# LoRa-E5-Sensor.net
KiCad netlist of a schematic drawn in EAGLE
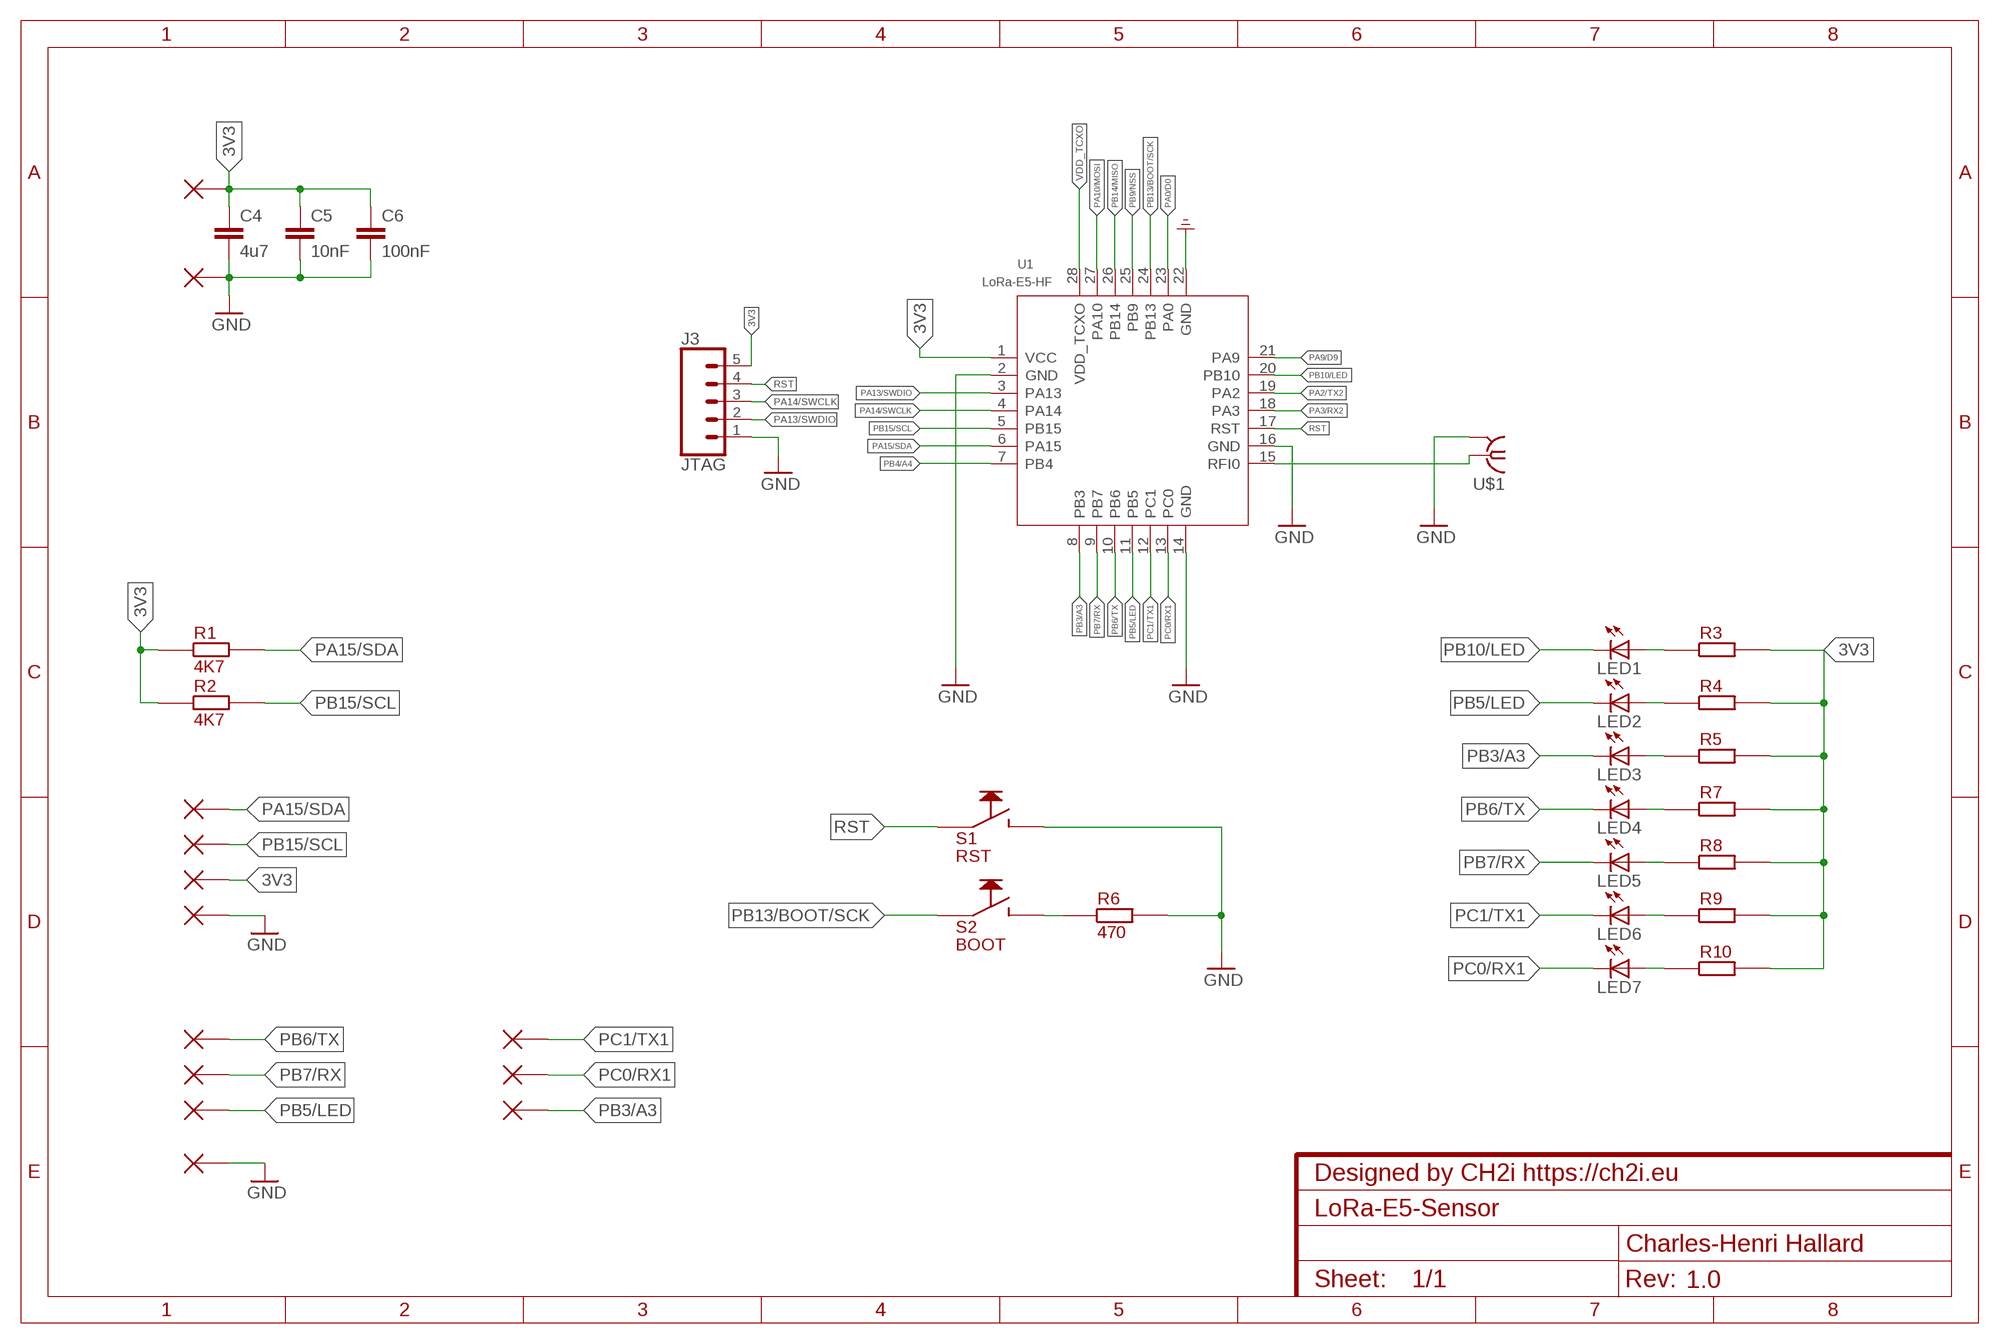
[diagram p0: schematic, sheet 1]

(export (version "E")
  (design (tool "Eeschema 10.0.6"))
  (components
    (comp (ref "C4")
      (value "4u7")
      (footprint "eagle-import:C1206")
      (libsource (lib "eagle-import") (part "SMD-C-1206"))
    )
    (comp (ref "C5")
      (value "10nF")
      (footprint "eagle-import:C1206")
      (libsource (lib "eagle-import") (part "SMD-C-1206"))
    )
    (comp (ref "C6")
      (value "100nF")
      (footprint "eagle-import:C1206")
      (libsource (lib "eagle-import") (part "SMD-C-1206"))
    )
    (comp (ref "J3")
      (value "JTAG")
      (footprint "eagle-import:1X05_LOCK")
      (libsource (lib "eagle-import") (part "CONN_05LOCK"))
    )
    (comp (ref "LED1")
      (value "SMD-LED-1206")
      (footprint "eagle-import:LED_1206")
      (libsource (lib "eagle-import") (part "SMD-LED-1206"))
    )
    (comp (ref "LED2")
      (value "SMD-LED-1206")
      (footprint "eagle-import:LED_1206")
      (libsource (lib "eagle-import") (part "SMD-LED-1206"))
    )
    (comp (ref "LED3")
      (value "SMD-LED-1206")
      (footprint "eagle-import:LED_1206")
      (libsource (lib "eagle-import") (part "SMD-LED-1206"))
    )
    (comp (ref "LED4")
      (value "SMD-LED-1206")
      (footprint "eagle-import:LED_1206")
      (libsource (lib "eagle-import") (part "SMD-LED-1206"))
    )
    (comp (ref "LED5")
      (value "SMD-LED-1206")
      (footprint "eagle-import:LED_1206")
      (libsource (lib "eagle-import") (part "SMD-LED-1206"))
    )
    (comp (ref "LED6")
      (value "SMD-LED-1206")
      (footprint "eagle-import:LED_1206")
      (libsource (lib "eagle-import") (part "SMD-LED-1206"))
    )
    (comp (ref "LED7")
      (value "SMD-LED-1206")
      (footprint "eagle-import:LED_1206")
      (libsource (lib "eagle-import") (part "SMD-LED-1206"))
    )
    (comp (ref "P1")
      (value "PIN")
      (footprint "eagle-import:PIN")
      (libsource (lib "eagle-import") (part "PIN"))
    )
    (comp (ref "P2")
      (value "PIN")
      (footprint "eagle-import:PIN")
      (libsource (lib "eagle-import") (part "PIN"))
    )
    (comp (ref "P3")
      (value "PIN")
      (footprint "eagle-import:PIN")
      (libsource (lib "eagle-import") (part "PIN"))
    )
    (comp (ref "P4")
      (value "PIN")
      (footprint "eagle-import:PIN")
      (libsource (lib "eagle-import") (part "PIN"))
    )
    (comp (ref "P5")
      (value "PIN")
      (footprint "eagle-import:PIN")
      (libsource (lib "eagle-import") (part "PIN"))
    )
    (comp (ref "P6")
      (value "PIN")
      (footprint "eagle-import:PIN")
      (libsource (lib "eagle-import") (part "PIN"))
    )
    (comp (ref "P7")
      (value "PIN")
      (footprint "eagle-import:PIN")
      (libsource (lib "eagle-import") (part "PIN"))
    )
    (comp (ref "P8")
      (value "PIN")
      (footprint "eagle-import:PIN")
      (libsource (lib "eagle-import") (part "PIN"))
    )
    (comp (ref "P9")
      (value "PIN")
      (footprint "eagle-import:PIN")
      (libsource (lib "eagle-import") (part "PIN"))
    )
    (comp (ref "P10")
      (value "PIN")
      (footprint "eagle-import:PIN")
      (libsource (lib "eagle-import") (part "PIN"))
    )
    (comp (ref "P11")
      (value "PIN")
      (footprint "eagle-import:PIN")
      (libsource (lib "eagle-import") (part "PIN"))
    )
    (comp (ref "P12")
      (value "PIN")
      (footprint "eagle-import:PIN")
      (libsource (lib "eagle-import") (part "PIN"))
    )
    (comp (ref "P13")
      (value "PIN")
      (footprint "eagle-import:PIN")
      (libsource (lib "eagle-import") (part "PIN"))
    )
    (comp (ref "R1")
      (value "4K7")
      (footprint "eagle-import:R0603")
      (libsource (lib "eagle-import") (part "SMD-RR0603"))
    )
    (comp (ref "R2")
      (value "4K7")
      (footprint "eagle-import:R0603")
      (libsource (lib "eagle-import") (part "SMD-RR0603"))
    )
    (comp (ref "R3")
      (value "SMD-RR0603")
      (footprint "eagle-import:R0603")
      (libsource (lib "eagle-import") (part "SMD-RR0603"))
    )
    (comp (ref "R4")
      (value "SMD-RR0603")
      (footprint "eagle-import:R0603")
      (libsource (lib "eagle-import") (part "SMD-RR0603"))
    )
    (comp (ref "R5")
      (value "SMD-RR0603")
      (footprint "eagle-import:R0603")
      (libsource (lib "eagle-import") (part "SMD-RR0603"))
    )
    (comp (ref "R6")
      (value "470")
      (footprint "eagle-import:C1206")
      (libsource (lib "eagle-import") (part "SMD-RR1206"))
    )
    (comp (ref "R7")
      (value "SMD-RR0603")
      (footprint "eagle-import:R0603")
      (libsource (lib "eagle-import") (part "SMD-RR0603"))
    )
    (comp (ref "R8")
      (value "SMD-RR0603")
      (footprint "eagle-import:R0603")
      (libsource (lib "eagle-import") (part "SMD-RR0603"))
    )
    (comp (ref "R9")
      (value "SMD-RR0603")
      (footprint "eagle-import:R0603")
      (libsource (lib "eagle-import") (part "SMD-RR0603"))
    )
    (comp (ref "R10")
      (value "SMD-RR0603")
      (footprint "eagle-import:R0603")
      (libsource (lib "eagle-import") (part "SMD-RR0603"))
    )
    (comp (ref "S1")
      (value "RST")
      (footprint "eagle-import:SMD-PUSH-BUTTON-ILS-3X6X2,5")
      (libsource (lib "eagle-import") (part "SMD-PUSH-BUTTONILS-3X6X2,5"))
    )
    (comp (ref "S2")
      (value "BOOT")
      (footprint "eagle-import:SMD-PUSH-BUTTON-ILS-3X6X2,5")
      (libsource (lib "eagle-import") (part "SMD-PUSH-BUTTONILS-3X6X2,5"))
    )
    (comp (ref "U$1")
      (value "SMAU.FL")
      (footprint "eagle-import:U.FL_SMT")
      (libsource (lib "eagle-import") (part "SMAU.FL"))
    )
    (comp (ref "U1")
      (value "LoRa-E5-HF")
      (footprint "eagle-import:MOUDLE28P-1.25-12X12X2.5MM")
      (libsource (lib "eagle-import") (part "MOUDLE_LORA_E5"))
    )
  )
  (nets
    (net (code "1") (name "3V3") (class "Default")
      (node (ref "C4") (pin "1") (pinfunction "1_1") (pintype "passive"))
      (node (ref "C5") (pin "1") (pinfunction "1_1") (pintype "passive"))
      (node (ref "C6") (pin "1") (pinfunction "1_1") (pintype "passive"))
      (node (ref "J3") (pin "5") (pinfunction "5_5") (pintype "passive"))
      (node (ref "P4") (pin "P$1") (pinfunction "P$1_P$1") (pintype "bidirectional"))
      (node (ref "P5") (pin "P$1") (pinfunction "P$1_P$1") (pintype "bidirectional"))
      (node (ref "R1") (pin "1") (pinfunction "P$1_1") (pintype "passive"))
      (node (ref "R10") (pin "2") (pinfunction "P$3_2") (pintype "passive"))
      (node (ref "R2") (pin "1") (pinfunction "P$1_1") (pintype "passive"))
      (node (ref "R3") (pin "2") (pinfunction "P$3_2") (pintype "passive"))
      (node (ref "R4") (pin "2") (pinfunction "P$3_2") (pintype "passive"))
      (node (ref "R5") (pin "2") (pinfunction "P$3_2") (pintype "passive"))
      (node (ref "R7") (pin "2") (pinfunction "P$3_2") (pintype "passive"))
      (node (ref "R8") (pin "2") (pinfunction "P$3_2") (pintype "passive"))
      (node (ref "R9") (pin "2") (pinfunction "P$3_2") (pintype "passive"))
      (node (ref "U1") (pin "1") (pinfunction "VCC_1") (pintype "bidirectional"))
    )
    (net (code "2") (name "GND") (class "Default")
      (node (ref "C4") (pin "2") (pinfunction "2_2") (pintype "passive"))
      (node (ref "C5") (pin "2") (pinfunction "2_2") (pintype "passive"))
      (node (ref "C6") (pin "2") (pinfunction "2_2") (pintype "passive"))
      (node (ref "J3") (pin "1") (pinfunction "1_1") (pintype "passive"))
      (node (ref "P1") (pin "P$1") (pinfunction "P$1_P$1") (pintype "bidirectional"))
      (node (ref "P6") (pin "P$1") (pinfunction "P$1_P$1") (pintype "bidirectional"))
      (node (ref "P9") (pin "P$1") (pinfunction "P$1_P$1") (pintype "bidirectional"))
      (node (ref "R6") (pin "2") (pinfunction "P$3_2") (pintype "passive"))
      (node (ref "S1") (pin "P$2") (pinfunction "P$2_P$2") (pintype "bidirectional"))
      (node (ref "U$1") (pin "GND1") (pinfunction "SHIELD_GND1") (pintype "passive"))
      (node (ref "U$1") (pin "GND2") (pinfunction "SHIELD_GND2") (pintype "passive"))
      (node (ref "U1") (pin "14") (pinfunction "GND_14") (pintype "bidirectional"))
      (node (ref "U1") (pin "16") (pinfunction "GND_16") (pintype "bidirectional"))
      (node (ref "U1") (pin "2") (pinfunction "GND_2") (pintype "bidirectional"))
      (node (ref "U1") (pin "22") (pinfunction "GND_22") (pintype "bidirectional"))
    )
    (net (code "3") (name "Net-(R3-P$1)") (class "Default")
      (node (ref "LED1") (pin "A") (pinfunction "A_A") (pintype "passive"))
      (node (ref "R3") (pin "1") (pinfunction "P$1_1") (pintype "passive"))
    )
    (net (code "4") (name "Net-(R4-P$1)") (class "Default")
      (node (ref "LED2") (pin "A") (pinfunction "A_A") (pintype "passive"))
      (node (ref "R4") (pin "1") (pinfunction "P$1_1") (pintype "passive"))
    )
    (net (code "5") (name "Net-(R5-P$1)") (class "Default")
      (node (ref "LED3") (pin "A") (pinfunction "A_A") (pintype "passive"))
      (node (ref "R5") (pin "1") (pinfunction "P$1_1") (pintype "passive"))
    )
    (net (code "6") (name "Net-(R6-P$1)") (class "Default")
      (node (ref "R6") (pin "1") (pinfunction "P$1_1") (pintype "passive"))
      (node (ref "S2") (pin "P$2") (pinfunction "P$2_P$2") (pintype "bidirectional"))
    )
    (net (code "7") (name "Net-(R7-P$1)") (class "Default")
      (node (ref "LED4") (pin "A") (pinfunction "A_A") (pintype "passive"))
      (node (ref "R7") (pin "1") (pinfunction "P$1_1") (pintype "passive"))
    )
    (net (code "8") (name "Net-(R8-P$1)") (class "Default")
      (node (ref "LED5") (pin "A") (pinfunction "A_A") (pintype "passive"))
      (node (ref "R8") (pin "1") (pinfunction "P$1_1") (pintype "passive"))
    )
    (net (code "9") (name "Net-(R9-P$1)") (class "Default")
      (node (ref "LED6") (pin "A") (pinfunction "A_A") (pintype "passive"))
      (node (ref "R9") (pin "1") (pinfunction "P$1_1") (pintype "passive"))
    )
    (net (code "10") (name "Net-(R10-P$1)") (class "Default")
      (node (ref "LED7") (pin "A") (pinfunction "A_A") (pintype "passive"))
      (node (ref "R10") (pin "1") (pinfunction "P$1_1") (pintype "passive"))
    )
    (net (code "11") (name "Net-(U$1-ANT)") (class "Default")
      (node (ref "U$1") (pin "SIG") (pinfunction "ANT_SIG") (pintype "passive"))
      (node (ref "U1") (pin "15") (pinfunction "RFI0_15") (pintype "bidirectional"))
    )
    (net (code "12") (name "PA0{slash}D0") (class "Default")
      (node (ref "U1") (pin "23") (pinfunction "PA0_23") (pintype "bidirectional"))
    )
    (net (code "13") (name "PA2{slash}TX2") (class "Default")
      (node (ref "U1") (pin "19") (pinfunction "PA2_19") (pintype "bidirectional"))
    )
    (net (code "14") (name "PA3{slash}RX2") (class "Default")
      (node (ref "U1") (pin "18") (pinfunction "PA3_18") (pintype "bidirectional"))
    )
    (net (code "15") (name "PA9{slash}D9") (class "Default")
      (node (ref "U1") (pin "21") (pinfunction "PA9_21") (pintype "bidirectional"))
    )
    (net (code "16") (name "PA10{slash}MOSI") (class "Default")
      (node (ref "U1") (pin "27") (pinfunction "PA10_27") (pintype "bidirectional"))
    )
    (net (code "17") (name "PA13{slash}SWDIO") (class "Default")
      (node (ref "J3") (pin "2") (pinfunction "2_2") (pintype "passive"))
      (node (ref "U1") (pin "3") (pinfunction "PA13_3") (pintype "bidirectional"))
    )
    (net (code "18") (name "PA14{slash}SWCLK") (class "Default")
      (node (ref "J3") (pin "3") (pinfunction "3_3") (pintype "passive"))
      (node (ref "U1") (pin "4") (pinfunction "PA14_4") (pintype "bidirectional"))
    )
    (net (code "19") (name "PA15{slash}SDA") (class "Default")
      (node (ref "P2") (pin "P$1") (pinfunction "P$1_P$1") (pintype "bidirectional"))
      (node (ref "R1") (pin "2") (pinfunction "P$3_2") (pintype "passive"))
      (node (ref "U1") (pin "6") (pinfunction "PA15_6") (pintype "bidirectional"))
    )
    (net (code "20") (name "PB3{slash}A3") (class "Default")
      (node (ref "LED3") (pin "C") (pinfunction "C_C") (pintype "passive"))
      (node (ref "P13") (pin "P$1") (pinfunction "P$1_P$1") (pintype "bidirectional"))
      (node (ref "U1") (pin "8") (pinfunction "PB3_8") (pintype "bidirectional"))
    )
    (net (code "21") (name "PB4{slash}A4") (class "Default")
      (node (ref "U1") (pin "7") (pinfunction "PB4_7") (pintype "bidirectional"))
    )
    (net (code "22") (name "PB5{slash}LED") (class "Default")
      (node (ref "LED2") (pin "C") (pinfunction "C_C") (pintype "passive"))
      (node (ref "P12") (pin "P$1") (pinfunction "P$1_P$1") (pintype "bidirectional"))
      (node (ref "U1") (pin "11") (pinfunction "PB5_11") (pintype "bidirectional"))
    )
    (net (code "23") (name "PB6{slash}TX") (class "Default")
      (node (ref "LED4") (pin "C") (pinfunction "C_C") (pintype "passive"))
      (node (ref "P7") (pin "P$1") (pinfunction "P$1_P$1") (pintype "bidirectional"))
      (node (ref "U1") (pin "10") (pinfunction "PB6_10") (pintype "bidirectional"))
    )
    (net (code "24") (name "PB7{slash}RX") (class "Default")
      (node (ref "LED5") (pin "C") (pinfunction "C_C") (pintype "passive"))
      (node (ref "P8") (pin "P$1") (pinfunction "P$1_P$1") (pintype "bidirectional"))
      (node (ref "U1") (pin "9") (pinfunction "PB7_9") (pintype "bidirectional"))
    )
    (net (code "25") (name "PB9{slash}NSS") (class "Default")
      (node (ref "U1") (pin "25") (pinfunction "PB9_25") (pintype "bidirectional"))
    )
    (net (code "26") (name "PB10{slash}LED") (class "Default")
      (node (ref "LED1") (pin "C") (pinfunction "C_C") (pintype "passive"))
      (node (ref "U1") (pin "20") (pinfunction "PB10_20") (pintype "bidirectional"))
    )
    (net (code "27") (name "PB13{slash}BOOT{slash}SCK") (class "Default")
      (node (ref "S2") (pin "P$1") (pinfunction "P$1_P$1") (pintype "bidirectional"))
      (node (ref "U1") (pin "24") (pinfunction "PB13_24") (pintype "bidirectional"))
    )
    (net (code "28") (name "PB14{slash}MISO") (class "Default")
      (node (ref "U1") (pin "26") (pinfunction "PB14_26") (pintype "bidirectional"))
    )
    (net (code "29") (name "PB15{slash}SCL") (class "Default")
      (node (ref "P3") (pin "P$1") (pinfunction "P$1_P$1") (pintype "bidirectional"))
      (node (ref "R2") (pin "2") (pinfunction "P$3_2") (pintype "passive"))
      (node (ref "U1") (pin "5") (pinfunction "PB15_5") (pintype "bidirectional"))
    )
    (net (code "30") (name "PC0{slash}RX1") (class "Default")
      (node (ref "LED7") (pin "C") (pinfunction "C_C") (pintype "passive"))
      (node (ref "P11") (pin "P$1") (pinfunction "P$1_P$1") (pintype "bidirectional"))
      (node (ref "U1") (pin "13") (pinfunction "PC0_13") (pintype "bidirectional"))
    )
    (net (code "31") (name "PC1{slash}TX1") (class "Default")
      (node (ref "LED6") (pin "C") (pinfunction "C_C") (pintype "passive"))
      (node (ref "P10") (pin "P$1") (pinfunction "P$1_P$1") (pintype "bidirectional"))
      (node (ref "U1") (pin "12") (pinfunction "PC1_12") (pintype "bidirectional"))
    )
    (net (code "32") (name "RST") (class "Default")
      (node (ref "J3") (pin "4") (pinfunction "4_4") (pintype "passive"))
      (node (ref "S1") (pin "P$1") (pinfunction "P$1_P$1") (pintype "bidirectional"))
      (node (ref "U1") (pin "17") (pinfunction "RST_17") (pintype "bidirectional"))
    )
    (net (code "33") (name "VDD_TCXO") (class "Default")
      (node (ref "U1") (pin "28") (pinfunction "VDD_TCXO_28") (pintype "bidirectional"))
    )
  )
)
